# 38kHzSensorRevA1.net
KiCad netlist of a schematic drawn in EAGLE
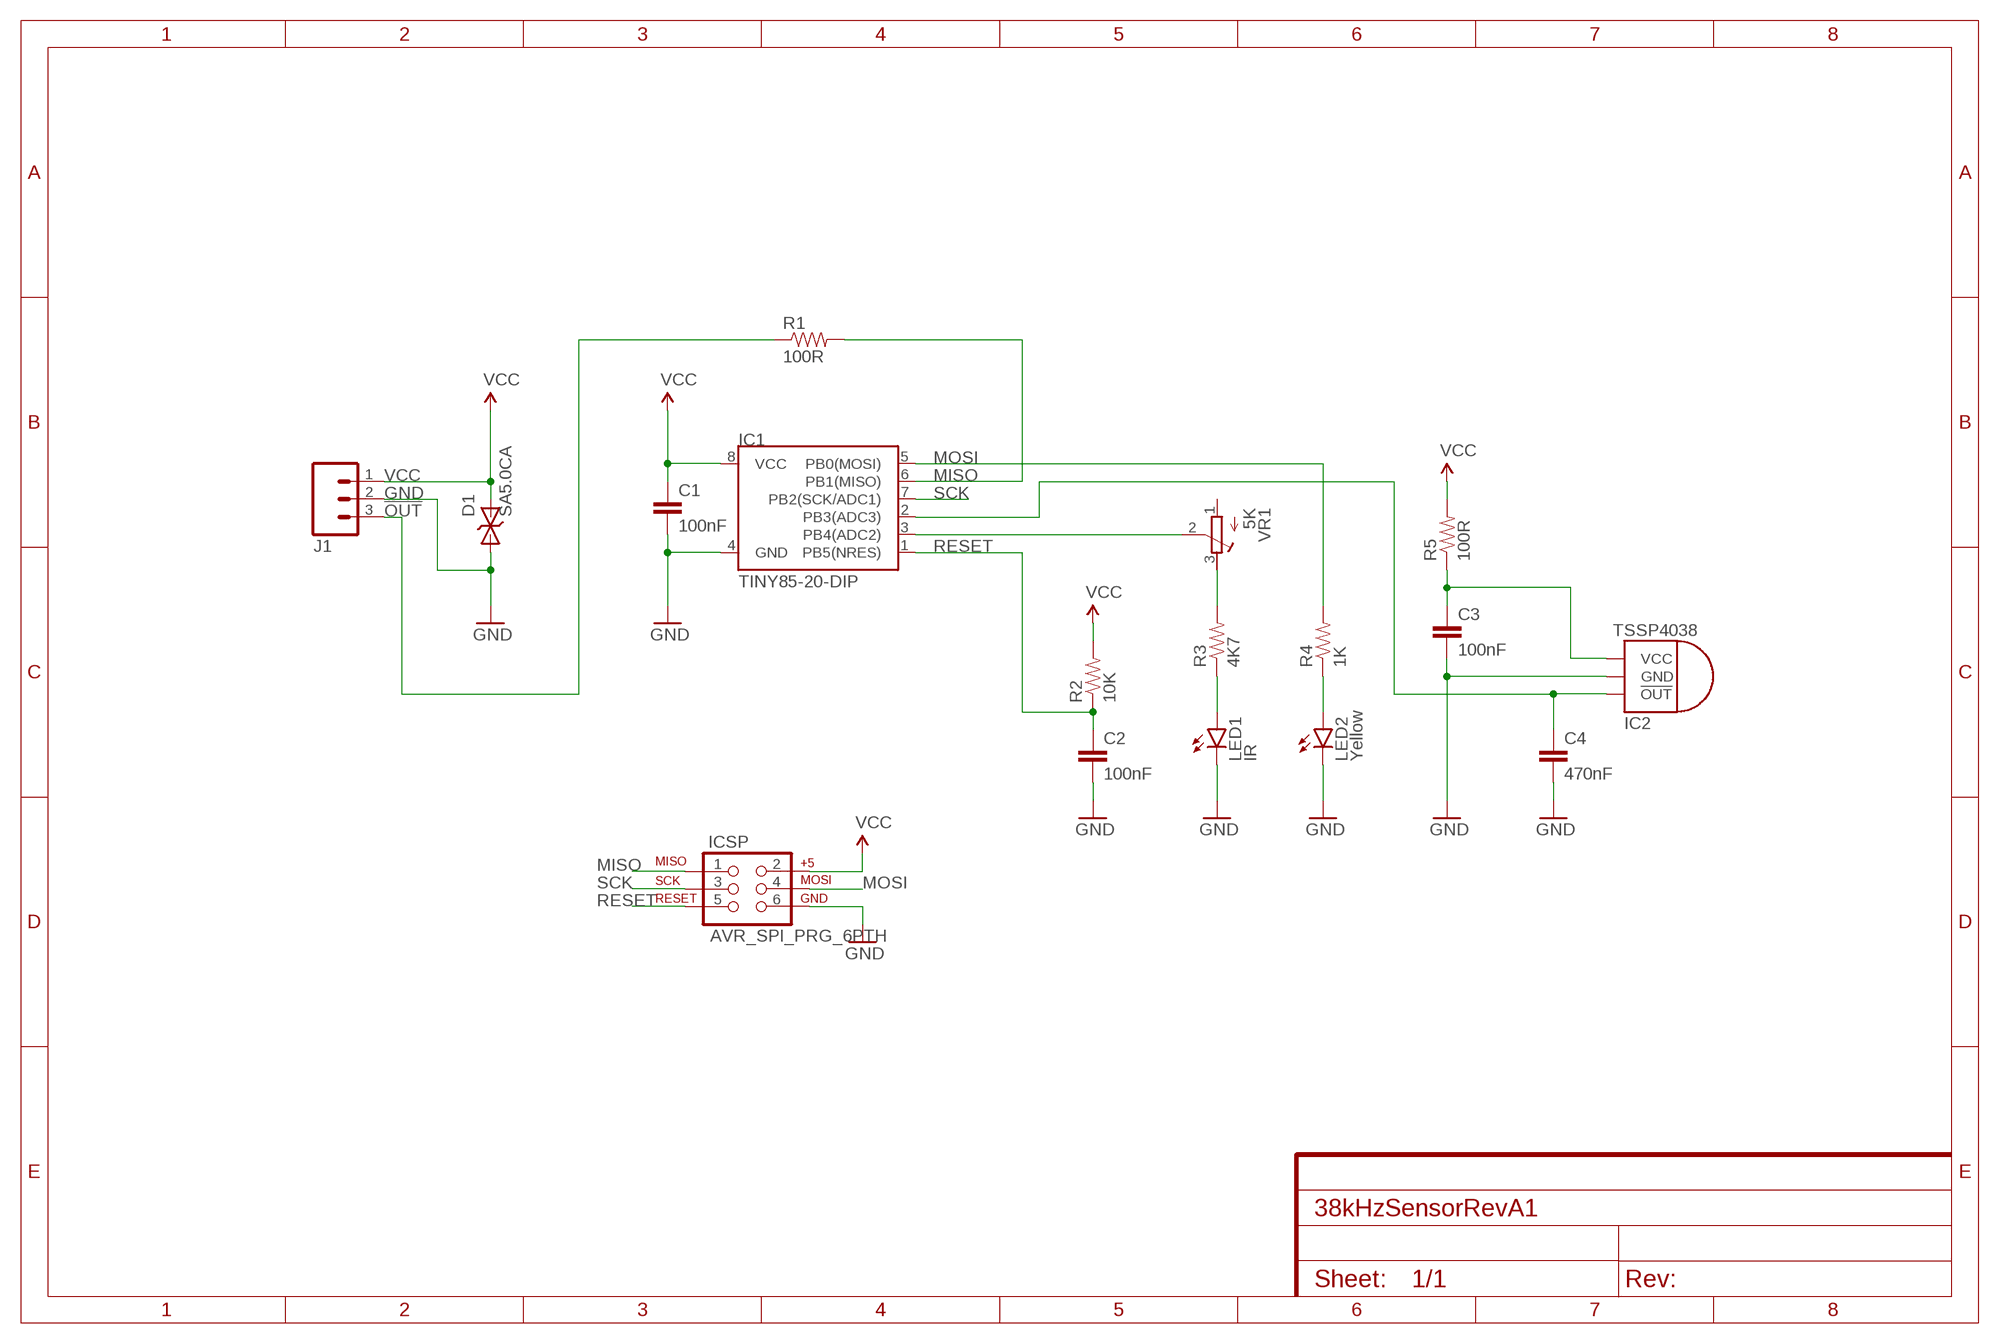
[diagram p0: schematic, sheet 1]

(export (version "E")
  (design (tool "Eeschema 10.0.6"))
  (components
    (comp (ref "C1")
      (value "100nF")
      (footprint "eagle-import:CAP-PTH-SMALL")
      (libsource (lib "eagle-import") (part "CAPPTH"))
    )
    (comp (ref "C2")
      (value "100nF")
      (footprint "eagle-import:CAP-PTH-SMALL")
      (libsource (lib "eagle-import") (part "CAPPTH"))
    )
    (comp (ref "C3")
      (value "100nF")
      (footprint "eagle-import:CAP-PTH-SMALL")
      (libsource (lib "eagle-import") (part "CAPPTH"))
    )
    (comp (ref "C4")
      (value "470nF")
      (footprint "eagle-import:CAP-PTH-5MM")
      (libsource (lib "eagle-import") (part "CAPPTH1"))
    )
    (comp (ref "D1")
      (value "SA5.0CA")
      (footprint "eagle-import:DO41_TVS")
      (libsource (lib "eagle-import") (part "SA5.0CA"))
    )
    (comp (ref "IC1")
      (value "TINY85-20-DIP")
      (footprint "eagle-import:DIP08")
      (libsource (lib "eagle-import") (part "ATTINY45TINY85-20-DIP"))
    )
    (comp (ref "IC2")
      (value "TSSP4038EDGE")
      (footprint "eagle-import:TSSP4038_PKG_EDGE")
      (libsource (lib "eagle-import") (part "TSSP4038EDGE"))
    )
    (comp (ref "ICSP")
      (value "AVR_SPI_PRG_6PTH")
      (footprint "eagle-import:2X3")
      (libsource (lib "eagle-import") (part "AVR_SPI_PRG_6PTH"))
    )
    (comp (ref "J1")
      (value "M03PTH")
      (footprint "eagle-import:1X03")
      (libsource (lib "eagle-import") (part "M03PTH"))
    )
    (comp (ref "LED1")
      (value "IR")
      (footprint "eagle-import:LED5MM")
      (libsource (lib "eagle-import") (part "LED5MM"))
    )
    (comp (ref "LED2")
      (value "Yellow")
      (footprint "eagle-import:LED3MM")
      (libsource (lib "eagle-import") (part "LED3MM"))
    )
    (comp (ref "R1")
      (value "100R")
      (footprint "eagle-import:AXIAL-0.4")
      (libsource (lib "eagle-import") (part "RESISTORPTH-1/4W"))
    )
    (comp (ref "R2")
      (value "10K")
      (footprint "eagle-import:AXIAL-0.4")
      (libsource (lib "eagle-import") (part "RESISTORPTH-1/4W"))
    )
    (comp (ref "R3")
      (value "4K7")
      (footprint "eagle-import:AXIAL-0.4")
      (libsource (lib "eagle-import") (part "RESISTORPTH-1/4W"))
    )
    (comp (ref "R4")
      (value "1K")
      (footprint "eagle-import:AXIAL-0.4")
      (libsource (lib "eagle-import") (part "RESISTORPTH-1/4W"))
    )
    (comp (ref "R5")
      (value "100R")
      (footprint "eagle-import:AXIAL-0.4")
      (libsource (lib "eagle-import") (part "RESISTORPTH-1/4W"))
    )
    (comp (ref "VR1")
      (value "5K")
      (footprint "eagle-import:RTRIM3296X")
      (libsource (lib "eagle-import") (part "R-TRIMM3296X"))
    )
  )
  (nets
    (net (code "1") (name "/MISO") (class "Default")
      (node (ref "IC1") (pin "6") (pinfunction "PB1(MISO)_6") (pintype "bidirectional"))
      (node (ref "ICSP") (pin "1") (pinfunction "1_1") (pintype "passive"))
      (node (ref "R1") (pin "P$2") (pinfunction "2_P$2") (pintype "passive"))
    )
    (net (code "2") (name "/MOSI") (class "Default")
      (node (ref "IC1") (pin "5") (pinfunction "PB0(MOSI)_5") (pintype "bidirectional"))
      (node (ref "ICSP") (pin "4") (pinfunction "4_4") (pintype "passive"))
      (node (ref "R4") (pin "P$2") (pinfunction "2_P$2") (pintype "passive"))
    )
    (net (code "3") (name "/RESET") (class "Default")
      (node (ref "C2") (pin "1") (pinfunction "1_1") (pintype "passive"))
      (node (ref "IC1") (pin "1") (pinfunction "PB5(NRES)_1") (pintype "bidirectional"))
      (node (ref "ICSP") (pin "5") (pinfunction "5_5") (pintype "passive"))
      (node (ref "R2") (pin "P$1") (pinfunction "1_P$1") (pintype "passive"))
    )
    (net (code "4") (name "/SCK") (class "Default")
      (node (ref "IC1") (pin "7") (pinfunction "PB2(SCK/ADC1)_7") (pintype "bidirectional"))
      (node (ref "ICSP") (pin "3") (pinfunction "3_3") (pintype "passive"))
    )
    (net (code "5") (name "/~{OUT}") (class "Default")
      (node (ref "J1") (pin "3") (pinfunction "3_3") (pintype "passive"))
      (node (ref "R1") (pin "P$1") (pinfunction "1_P$1") (pintype "passive"))
    )
    (net (code "6") (name "GND") (class "Default")
      (node (ref "C1") (pin "2") (pinfunction "2_2") (pintype "passive"))
      (node (ref "C2") (pin "2") (pinfunction "2_2") (pintype "passive"))
      (node (ref "C3") (pin "2") (pinfunction "2_2") (pintype "passive"))
      (node (ref "C4") (pin "2") (pinfunction "2_2") (pintype "passive"))
      (node (ref "D1") (pin "A") (pinfunction "A_A") (pintype "passive"))
      (node (ref "IC1") (pin "4") (pinfunction "GND_4") (pintype "bidirectional"))
      (node (ref "IC2") (pin "GND") (pinfunction "GND_GND") (pintype "bidirectional"))
      (node (ref "ICSP") (pin "6") (pinfunction "6_6") (pintype "passive"))
      (node (ref "J1") (pin "2") (pinfunction "2_2") (pintype "passive"))
      (node (ref "LED1") (pin "K") (pinfunction "C_K") (pintype "passive"))
      (node (ref "LED2") (pin "K") (pinfunction "C_K") (pintype "passive"))
    )
    (net (code "7") (name "Net-(IC1-PB3(ADC3))") (class "Default")
      (node (ref "C4") (pin "1") (pinfunction "1_1") (pintype "passive"))
      (node (ref "IC1") (pin "2") (pinfunction "PB3(ADC3)_2") (pintype "bidirectional"))
      (node (ref "IC2") (pin "OUT") (pinfunction "~{OUT}_OUT") (pintype "bidirectional"))
    )
    (net (code "8") (name "Net-(IC1-PB4(ADC2))") (class "Default")
      (node (ref "IC1") (pin "3") (pinfunction "PB4(ADC2)_3") (pintype "bidirectional"))
      (node (ref "VR1") (pin "2") (pinfunction "S_2") (pintype "passive"))
    )
    (net (code "9") (name "Net-(R3-1)") (class "Default")
      (node (ref "LED1") (pin "A") (pinfunction "A_A") (pintype "passive"))
      (node (ref "R3") (pin "P$1") (pinfunction "1_P$1") (pintype "passive"))
    )
    (net (code "10") (name "Net-(R3-2)") (class "Default")
      (node (ref "R3") (pin "P$2") (pinfunction "2_P$2") (pintype "passive"))
      (node (ref "VR1") (pin "3") (pinfunction "E_3") (pintype "passive"))
    )
    (net (code "11") (name "Net-(R4-1)") (class "Default")
      (node (ref "LED2") (pin "A") (pinfunction "A_A") (pintype "passive"))
      (node (ref "R4") (pin "P$1") (pinfunction "1_P$1") (pintype "passive"))
    )
    (net (code "12") (name "Net-(R5-1)") (class "Default")
      (node (ref "C3") (pin "1") (pinfunction "1_1") (pintype "passive"))
      (node (ref "IC2") (pin "VCC") (pinfunction "VCC_VCC") (pintype "bidirectional"))
      (node (ref "R5") (pin "P$1") (pinfunction "1_P$1") (pintype "passive"))
    )
    (net (code "13") (name "VCC") (class "Default")
      (node (ref "C1") (pin "1") (pinfunction "1_1") (pintype "passive"))
      (node (ref "D1") (pin "C") (pinfunction "C_C") (pintype "passive"))
      (node (ref "IC1") (pin "8") (pinfunction "VCC_8") (pintype "bidirectional"))
      (node (ref "ICSP") (pin "2") (pinfunction "2_2") (pintype "passive"))
      (node (ref "J1") (pin "1") (pinfunction "1_1") (pintype "passive"))
      (node (ref "R2") (pin "P$2") (pinfunction "2_P$2") (pintype "passive"))
      (node (ref "R5") (pin "P$2") (pinfunction "2_P$2") (pintype "passive"))
    )
    (net (code "14") (name "unconnected-(VR1-A-Pad1)") (class "Default")
      (node (ref "VR1") (pin "1") (pinfunction "A_1") (pintype "passive"))
    )
  )
)
